# IO.net
KiCad netlist of a schematic drawn in Altium Designer
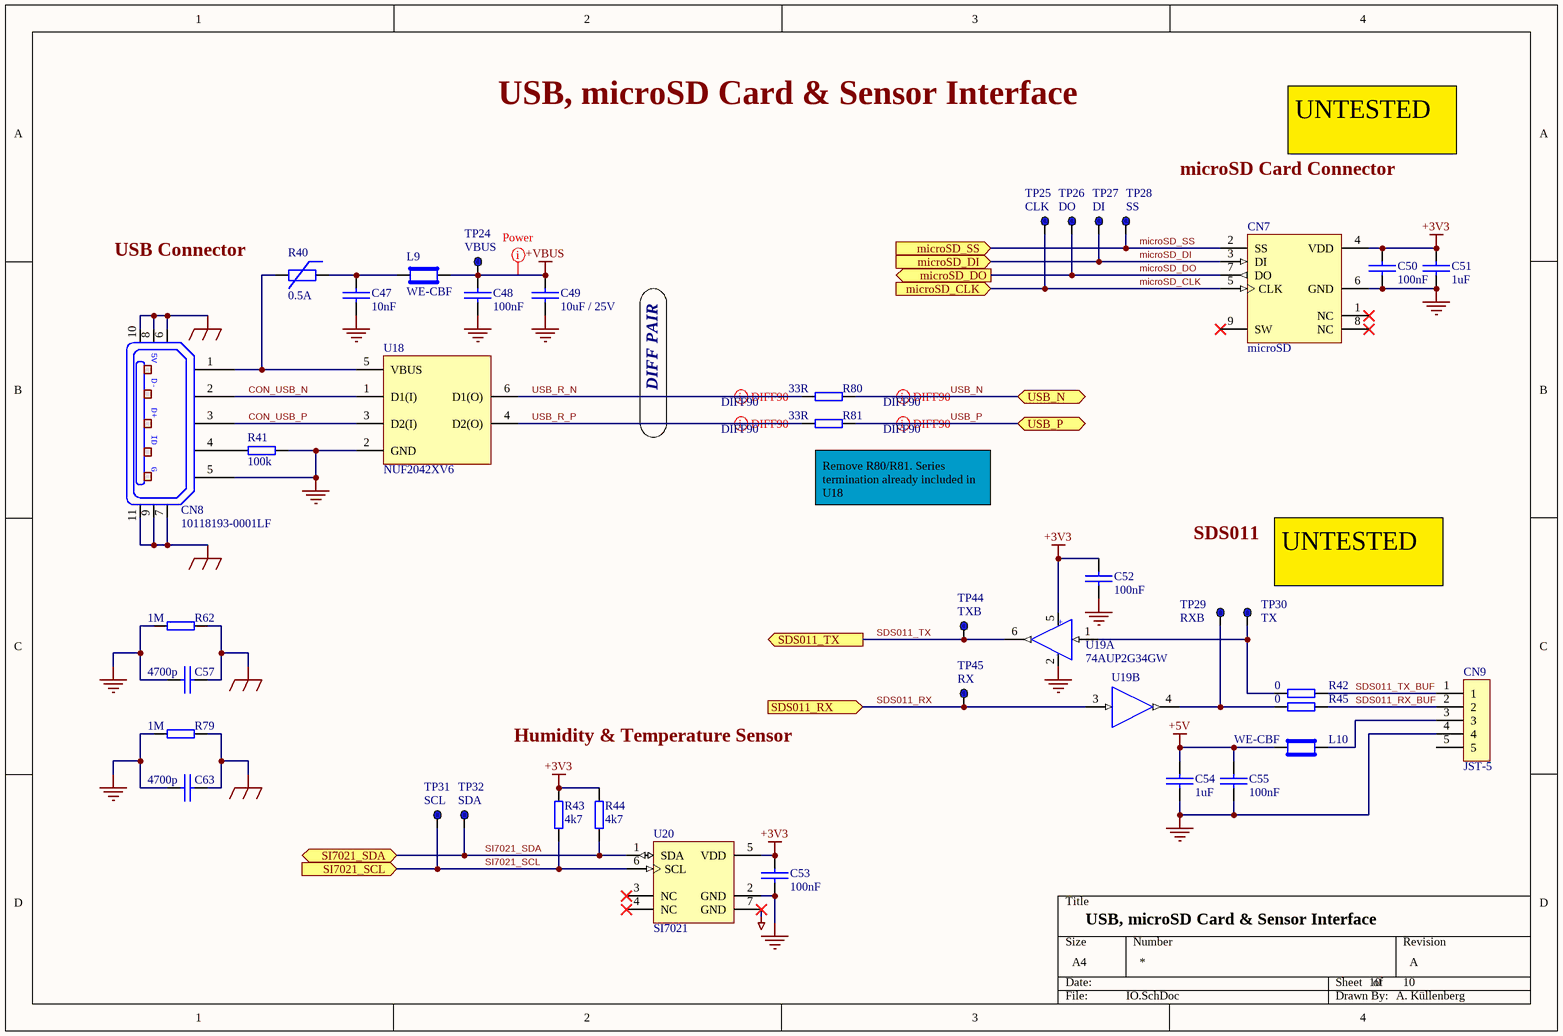
[diagram p0: IO.SchDoc]

(export (version "E")
  (design (tool "Eeschema 10.0.6"))
  (components
    (comp (ref "C47")
      (value "10nF")
      (footprint "C0603")
      (description "CAP CER 10000PF 50V X7R 0603")
      (fields (field (name "PART NUMBER") "06035C103KAT2A") (field (name "MANUFACTURER") "AVX Corporation"))
      (libsource (lib "AKLib") (part "CAP"))
    )
    (comp (ref "C48")
      (value "100nF")
      (footprint "C0603")
      (description "CAP CER 0.1UF 50V X7R 0603")
      (fields (field (name "PART NUMBER") "C0603C104K5RACTU") (field (name "MANUFACTURER") "Kemet"))
      (libsource (lib "AKLib") (part "CAP"))
    )
    (comp (ref "C49")
      (value "10uF / 25V")
      (footprint "C0603")
      (description "CAP CER 10UF 25V X5R 0603")
      (fields
        (field (name "PART NUMBER") "ZRB18AR61E106ME01L")
        (field (name "MANUFACTURER") "Murata Electronics North America")
      )
      (libsource (lib "AKLib") (part "CAP"))
    )
    (comp (ref "C50")
      (value "100nF")
      (footprint "C0603")
      (description "CAP CER 0.1UF 50V X7R 0603")
      (fields (field (name "PART NUMBER") "C0603C104K5RACTU") (field (name "MANUFACTURER") "Kemet"))
      (libsource (lib "AKLib") (part "CAP"))
    )
    (comp (ref "C51")
      (value "1uF")
      (footprint "C0603")
      (description "CAP CER 1UF 25V X7R 0603")
      (fields
        (field (name "PART NUMBER") "GCM188R71E105KA64D")
        (field (name "MANUFACTURER") "Murata Electronics North America")
      )
      (libsource (lib "AKLib") (part "CAP"))
    )
    (comp (ref "C52")
      (value "100nF")
      (footprint "C0603")
      (description "CAP CER 0.1UF 50V X7R 0603")
      (fields (field (name "PART NUMBER") "C0603C104K5RACTU") (field (name "MANUFACTURER") "Kemet"))
      (libsource (lib "AKLib") (part "CAP"))
    )
    (comp (ref "C53")
      (value "100nF")
      (footprint "C0603")
      (description "CAP CER 0.1UF 50V X7R 0603")
      (fields (field (name "PART NUMBER") "C0603C104K5RACTU") (field (name "MANUFACTURER") "Kemet"))
      (libsource (lib "AKLib") (part "CAP"))
    )
    (comp (ref "C54")
      (value "1uF")
      (footprint "C0603")
      (description "CAP CER 1UF 25V X7R 0603")
      (fields
        (field (name "PART NUMBER") "GCM188R71E105KA64D")
        (field (name "MANUFACTURER") "Murata Electronics North America")
      )
      (libsource (lib "AKLib") (part "CAP"))
    )
    (comp (ref "C55")
      (value "100nF")
      (footprint "C0603")
      (description "CAP CER 0.1UF 50V X7R 0603")
      (fields (field (name "PART NUMBER") "C0603C104K5RACTU") (field (name "MANUFACTURER") "Kemet"))
      (libsource (lib "AKLib") (part "CAP"))
    )
    (comp (ref "C57")
      (value "4700p")
      (footprint "C0805")
      (description "CAP CER 4700PF 1KV X7R 0805")
      (fields (field (name "PART NUMBER") "C0805V472KDRACTU") (field (name "MANUFACTURER") "KEMET"))
      (libsource (lib "AKLib") (part "CAP"))
    )
    (comp (ref "C63")
      (value "4700p")
      (footprint "C0805")
      (description "CAP CER 4700PF 1KV X7R 0805")
      (fields (field (name "PART NUMBER") "C0805V472KDRACTU") (field (name "MANUFACTURER") "KEMET"))
      (libsource (lib "AKLib") (part "CAP"))
    )
    (comp (ref "CN7")
      (value "microSD")
      (footprint "1050270001")
      (description "CONN MICRO SD CARD PUSH-PULL R/A")
      (fields (field (name "PART NUMBER") "1050270001") (field (name "MANUFACTURER") "Molex, LLC"))
      (libsource (lib "AKLib") (part "1050270001"))
    )
    (comp (ref "CN8")
      (value "10118193-0001LF")
      (footprint "10118193")
      (description "CONN USB MICRO B RECPT SMT R/A")
      (fields (field (name "MANUFACTURER") "Amphenol FCI"))
      (libsource (lib "AKLib") (part "10118193-0001LF"))
    )
    (comp (ref "CN9")
      (value "JST-5")
      (footprint "JST-5")
      (description "CONN HEADER XH TOP 5POS 2.5MM")
      (fields
        (field (name "PART NUMBER") "B5B-XH-A(LF)(SN)")
        (field (name "MANUFACTURER") "JST Sales America Inc.")
      )
      (libsource (lib "AKLib") (part "Header 1x5"))
    )
    (comp (ref "L9")
      (value "WE-CBF")
      (footprint "L0603")
      (description "FERRITE BEAD 600 OHM 0603 1LN")
      (fields (field (name "PART NUMBER") "742792651") (field (name "MANUFACTURER") "Wurth Electronics Inc."))
      (libsource (lib "AKLib") (part "FBEAD"))
    )
    (comp (ref "L10")
      (value "WE-CBF")
      (footprint "L0603")
      (description "FERRITE BEAD 600 OHM 0603 1LN")
      (fields (field (name "PART NUMBER") "742792651") (field (name "MANUFACTURER") "Wurth Electronics Inc."))
      (libsource (lib "AKLib") (part "FBEAD"))
    )
    (comp (ref "R40")
      (value "0.5A")
      (footprint "PTC-0603")
      (description "FUSE PTC RESET 500MA SMD 0603")
      (fields (field (name "PART NUMBER") "MF-FSMF050X-2") (field (name "MANUFACTURER") "Bourns Inc."))
      (libsource (lib "AKLib") (part "RES Varistor"))
    )
    (comp (ref "R41")
      (value "100k")
      (footprint "R0603")
      (description "RES SMD 100K OHM 1% 1/10W 0603")
      (fields (field (name "PART NUMBER") "RC0603FR-07100KL") (field (name "MANUFACTURER") "Yageo"))
      (libsource (lib "AKLib") (part "RES"))
    )
    (comp (ref "R42")
      (value "0")
      (footprint "R0603")
      (description "RES SMD 0.0OHM JUMPER 1/10W 0603")
      (fields (field (name "PART NUMBER") "RC0603JR-070RL") (field (name "MANUFACTURER") "Yageo"))
      (libsource (lib "AKLib") (part "RES"))
    )
    (comp (ref "R43")
      (value "4k7")
      (footprint "R0603")
      (description "RES SMD 4.7K OHM 1% 1/10W 0603")
      (fields (field (name "PART NUMBER") "CRCW06034K70FKEA") (field (name "MANUFACTURER") "Vishay Dale"))
      (libsource (lib "AKLib") (part "RES"))
    )
    (comp (ref "R44")
      (value "4k7")
      (footprint "R0603")
      (description "RES SMD 4.7K OHM 1% 1/10W 0603")
      (fields (field (name "PART NUMBER") "CRCW06034K70FKEA") (field (name "MANUFACTURER") "Vishay Dale"))
      (libsource (lib "AKLib") (part "RES"))
    )
    (comp (ref "R45")
      (value "0")
      (footprint "R0603")
      (description "RES SMD 0.0OHM JUMPER 1/10W 0603")
      (fields (field (name "PART NUMBER") "RC0603JR-070RL") (field (name "MANUFACTURER") "Yageo"))
      (libsource (lib "AKLib") (part "RES"))
    )
    (comp (ref "R62")
      (value "1M")
      (footprint "R0805")
      (description "RES SMD 1M OHM 1% 1/8W 0805")
      (fields (field (name "PART NUMBER") "RV0805FR-071ML") (field (name "MANUFACTURER") "Yageo"))
      (libsource (lib "AKLib") (part "RES"))
    )
    (comp (ref "R79")
      (value "1M")
      (footprint "R0805")
      (description "RES SMD 1M OHM 1% 1/8W 0805")
      (fields (field (name "PART NUMBER") "RV0805FR-071ML") (field (name "MANUFACTURER") "Yageo"))
      (libsource (lib "AKLib") (part "RES"))
    )
    (comp (ref "R80")
      (value "33R")
      (footprint "R0402")
      (description "RES SMD 33 OHM 1% 1/16W 0402")
      (fields (field (name "PART NUMBER") "RC0402FR-0733RL") (field (name "MANUFACTURER") "Yageo"))
      (libsource (lib "AKLib") (part "RES"))
    )
    (comp (ref "R81")
      (value "33R")
      (footprint "R0402")
      (description "RES SMD 33 OHM 1% 1/16W 0402")
      (fields (field (name "PART NUMBER") "RC0402FR-0733RL") (field (name "MANUFACTURER") "Yageo"))
      (libsource (lib "AKLib") (part "RES"))
    )
    (comp (ref "TP24")
      (value "VBUS")
      (footprint "TP_1mm")
      (fields (field (name "PART NUMBER") "TP"))
      (libsource (lib "AKLib") (part "TP"))
    )
    (comp (ref "TP25")
      (value "CLK")
      (footprint "TP_1mm")
      (fields (field (name "PART NUMBER") "TP"))
      (libsource (lib "AKLib") (part "TP"))
    )
    (comp (ref "TP26")
      (value "DO")
      (footprint "TP_1mm")
      (fields (field (name "PART NUMBER") "TP"))
      (libsource (lib "AKLib") (part "TP"))
    )
    (comp (ref "TP27")
      (value "DI")
      (footprint "TP_1mm")
      (fields (field (name "PART NUMBER") "TP"))
      (libsource (lib "AKLib") (part "TP"))
    )
    (comp (ref "TP28")
      (value "SS")
      (footprint "TP_1mm")
      (fields (field (name "PART NUMBER") "TP"))
      (libsource (lib "AKLib") (part "TP"))
    )
    (comp (ref "TP29")
      (value "RXB")
      (footprint "TP_1mm")
      (fields (field (name "PART NUMBER") "TP"))
      (libsource (lib "AKLib") (part "TP"))
    )
    (comp (ref "TP30")
      (value "TX")
      (footprint "TP_1mm")
      (fields (field (name "PART NUMBER") "TP"))
      (libsource (lib "AKLib") (part "TP"))
    )
    (comp (ref "TP31")
      (value "SCL")
      (footprint "TP_1mm")
      (fields (field (name "PART NUMBER") "TP"))
      (libsource (lib "AKLib") (part "TP"))
    )
    (comp (ref "TP32")
      (value "SDA")
      (footprint "TP_1mm")
      (fields (field (name "PART NUMBER") "TP"))
      (libsource (lib "AKLib") (part "TP"))
    )
    (comp (ref "TP44")
      (value "TXB")
      (footprint "TP_1mm")
      (fields (field (name "PART NUMBER") "TP"))
      (libsource (lib "AKLib") (part "TP"))
    )
    (comp (ref "TP45")
      (value "RX")
      (footprint "TP_1mm")
      (fields (field (name "PART NUMBER") "TP"))
      (libsource (lib "AKLib") (part "TP"))
    )
    (comp (ref "U18")
      (value "NUF2042XV6")
      (footprint "SOT-563")
      (description "FILTER RC(PI) 22 OHM/42PF SMD")
      (fields (field (name "PART NUMBER") "NUF2042XV6T1G") (field (name "MANUFACTURER") "ON Semiconductor"))
      (libsource (lib "AKLib") (part "NUF2042XV6"))
    )
    (comp (ref "U19")
      (value "74AUP2G34GW")
      (footprint "SOT363")
      (description "IC BUFF DL LOW PWR N-INV 6TSSOP")
      (fields
        (field (name "PART NUMBER") "74AUP2G34GW,125")
        (field (name "MANUFACTURER") "Nexperia USA Inc.")
      )
      (libsource (lib "AKLib") (part "74AUP2G34GW"))
    )
    (comp (ref "U20")
      (value "SI7021")
      (footprint "SI7021")
      (description "SENS HUMI/TEMP 3.6V I2C 3% 6DFN")
      (fields (field (name "PART NUMBER") "SI7021-A20-GM1") (field (name "MANUFACTURER") "Silicon Labs"))
      (libsource (lib "AKLib") (part "SI7021"))
    )
  )
  (nets
    (net (code "1") (name "+3V3") (class "Default")
      (node (ref "C50") (pin "2") (pinfunction "2_2") (pintype "passive"))
      (node (ref "C51") (pin "2") (pinfunction "2_2") (pintype "passive"))
      (node (ref "C52") (pin "2") (pinfunction "2_2") (pintype "passive"))
      (node (ref "C53") (pin "2") (pinfunction "2_2") (pintype "passive"))
      (node (ref "CN7") (pin "4") (pinfunction "VDD_4") (pintype "power_in"))
      (node (ref "R43") (pin "2") (pinfunction "2_2") (pintype "passive"))
      (node (ref "R44") (pin "2") (pinfunction "2_2") (pintype "passive"))
      (node (ref "U19") (pin "5") (pinfunction "5_5") (pintype "passive"))
      (node (ref "U20") (pin "5") (pinfunction "VDD_5") (pintype "power_in"))
    )
    (net (code "2") (name "+5V") (class "Default")
      (node (ref "C54") (pin "1") (pinfunction "1_1") (pintype "passive"))
      (node (ref "C55") (pin "1") (pinfunction "1_1") (pintype "passive"))
      (node (ref "L10") (pin "1") (pinfunction "1_1") (pintype "passive"))
    )
    (net (code "3") (name "+VBUS") (class "Default")
      (node (ref "C48") (pin "2") (pinfunction "2_2") (pintype "passive"))
      (node (ref "C49") (pin "2") (pinfunction "2_2") (pintype "passive"))
      (node (ref "L9") (pin "2") (pinfunction "2_2") (pintype "passive"))
      (node (ref "TP24") (pin "1") (pinfunction "1_1") (pintype "passive"))
    )
    (net (code "4") (name "/CON_USB_N") (class "Default")
      (node (ref "CN8") (pin "2") (pinfunction "2_2") (pintype "passive"))
      (node (ref "U18") (pin "1") (pinfunction "D1(I)_1") (pintype "passive"))
    )
    (net (code "5") (name "/CON_USB_P") (class "Default")
      (node (ref "CN8") (pin "3") (pinfunction "3_3") (pintype "passive"))
      (node (ref "U18") (pin "3") (pinfunction "D2(I)_3") (pintype "passive"))
    )
    (net (code "6") (name "/SDS011_RX") (class "Default")
      (node (ref "TP45") (pin "1") (pinfunction "1_1") (pintype "passive"))
      (node (ref "U19") (pin "3") (pinfunction "3_3") (pintype "input"))
    )
    (net (code "7") (name "/SDS011_RX_BUF") (class "Default")
      (node (ref "CN9") (pin "2") (pinfunction "2_2") (pintype "passive"))
      (node (ref "R45") (pin "2") (pinfunction "2_2") (pintype "passive"))
    )
    (net (code "8") (name "/SDS011_TX") (class "Default")
      (node (ref "TP44") (pin "1") (pinfunction "1_1") (pintype "passive"))
      (node (ref "U19") (pin "6") (pinfunction "6_6") (pintype "output"))
    )
    (net (code "9") (name "/SDS011_TX_BUF") (class "Default")
      (node (ref "CN9") (pin "1") (pinfunction "1_1") (pintype "passive"))
      (node (ref "R42") (pin "2") (pinfunction "2_2") (pintype "passive"))
    )
    (net (code "10") (name "/SI7021_SCL") (class "Default")
      (node (ref "R43") (pin "1") (pinfunction "1_1") (pintype "passive"))
      (node (ref "TP31") (pin "1") (pinfunction "1_1") (pintype "passive"))
      (node (ref "U20") (pin "6") (pinfunction "SCL_6") (pintype "input"))
    )
    (net (code "11") (name "/SI7021_SDA") (class "Default")
      (node (ref "R44") (pin "1") (pinfunction "1_1") (pintype "passive"))
      (node (ref "TP32") (pin "1") (pinfunction "1_1") (pintype "passive"))
      (node (ref "U20") (pin "1") (pinfunction "SDA_1") (pintype "bidirectional"))
    )
    (net (code "12") (name "/USB_N") (class "Default")
      (node (ref "R80") (pin "2") (pinfunction "2_2") (pintype "passive"))
    )
    (net (code "13") (name "/USB_P") (class "Default")
      (node (ref "R81") (pin "2") (pinfunction "2_2") (pintype "passive"))
    )
    (net (code "14") (name "/USB_R_N") (class "Default")
      (node (ref "R80") (pin "1") (pinfunction "1_1") (pintype "passive"))
      (node (ref "U18") (pin "6") (pinfunction "D1(O)_6") (pintype "passive"))
    )
    (net (code "15") (name "/USB_R_P") (class "Default")
      (node (ref "R81") (pin "1") (pinfunction "1_1") (pintype "passive"))
      (node (ref "U18") (pin "4") (pinfunction "D2(O)_4") (pintype "passive"))
    )
    (net (code "16") (name "/microSD_CLK") (class "Default")
      (node (ref "CN7") (pin "5") (pinfunction "CLK_5") (pintype "input"))
      (node (ref "TP25") (pin "1") (pinfunction "1_1") (pintype "passive"))
    )
    (net (code "17") (name "/microSD_DI") (class "Default")
      (node (ref "CN7") (pin "3") (pinfunction "DI_3") (pintype "input"))
      (node (ref "TP27") (pin "1") (pinfunction "1_1") (pintype "passive"))
    )
    (net (code "18") (name "/microSD_DO") (class "Default")
      (node (ref "CN7") (pin "7") (pinfunction "DO_7") (pintype "output"))
      (node (ref "TP26") (pin "1") (pinfunction "1_1") (pintype "passive"))
    )
    (net (code "19") (name "/microSD_SS") (class "Default")
      (node (ref "CN7") (pin "2") (pinfunction "SS_2") (pintype "passive"))
      (node (ref "TP28") (pin "1") (pinfunction "1_1") (pintype "passive"))
    )
    (net (code "20") (name "GND") (class "Default")
      (node (ref "C47") (pin "1") (pinfunction "1_1") (pintype "passive"))
      (node (ref "C48") (pin "1") (pinfunction "1_1") (pintype "passive"))
      (node (ref "C49") (pin "1") (pinfunction "1_1") (pintype "passive"))
      (node (ref "C50") (pin "1") (pinfunction "1_1") (pintype "passive"))
      (node (ref "C51") (pin "1") (pinfunction "1_1") (pintype "passive"))
      (node (ref "C52") (pin "1") (pinfunction "1_1") (pintype "passive"))
      (node (ref "C53") (pin "1") (pinfunction "1_1") (pintype "passive"))
      (node (ref "C54") (pin "2") (pinfunction "2_2") (pintype "passive"))
      (node (ref "C55") (pin "2") (pinfunction "2_2") (pintype "passive"))
      (node (ref "C57") (pin "1") (pinfunction "1_1") (pintype "passive"))
      (node (ref "C63") (pin "1") (pinfunction "1_1") (pintype "passive"))
      (node (ref "CN7") (pin "6") (pinfunction "GND_6") (pintype "power_in"))
      (node (ref "CN8") (pin "5") (pinfunction "5_5") (pintype "passive"))
      (node (ref "CN9") (pin "4") (pinfunction "4_4") (pintype "passive"))
      (node (ref "R41") (pin "2") (pinfunction "2_2") (pintype "passive"))
      (node (ref "R62") (pin "1") (pinfunction "1_1") (pintype "passive"))
      (node (ref "R79") (pin "1") (pinfunction "1_1") (pintype "passive"))
      (node (ref "U18") (pin "2") (pinfunction "GND_2") (pintype "power_in"))
      (node (ref "U19") (pin "2") (pinfunction "2_2") (pintype "power_in"))
      (node (ref "U20") (pin "2") (pinfunction "GND_2") (pintype "power_in"))
    )
    (net (code "21") (name "Net-(C47-Pad2)") (class "Default")
      (node (ref "C47") (pin "2") (pinfunction "2_2") (pintype "passive"))
      (node (ref "L9") (pin "1") (pinfunction "1_1") (pintype "passive"))
      (node (ref "R40") (pin "1") (pinfunction "1_1") (pintype "passive"))
    )
    (net (code "22") (name "Net-(CN8-Pad4)") (class "Default")
      (node (ref "CN8") (pin "4") (pinfunction "4_4") (pintype "passive"))
      (node (ref "R41") (pin "1") (pinfunction "1_1") (pintype "passive"))
    )
    (net (code "23") (name "Net-(CN9-Pad3)") (class "Default")
      (node (ref "CN9") (pin "3") (pinfunction "3_3") (pintype "passive"))
      (node (ref "L10") (pin "2") (pinfunction "2_2") (pintype "passive"))
    )
    (net (code "24") (name "Net-(R42-Pad1)") (class "Default")
      (node (ref "R42") (pin "1") (pinfunction "1_1") (pintype "passive"))
      (node (ref "TP30") (pin "1") (pinfunction "1_1") (pintype "passive"))
      (node (ref "U19") (pin "1") (pinfunction "1_1") (pintype "input"))
    )
    (net (code "25") (name "Net-(R45-Pad1)") (class "Default")
      (node (ref "R45") (pin "1") (pinfunction "1_1") (pintype "passive"))
      (node (ref "TP29") (pin "1") (pinfunction "1_1") (pintype "passive"))
      (node (ref "U19") (pin "4") (pinfunction "4_4") (pintype "output"))
    )
    (net (code "26") (name "Net-(U18-VBUS)") (class "Default")
      (node (ref "CN8") (pin "1") (pinfunction "1_1") (pintype "passive"))
      (node (ref "R40") (pin "2") (pinfunction "2_2") (pintype "passive"))
      (node (ref "U18") (pin "5") (pinfunction "VBUS_5") (pintype "power_in"))
    )
    (net (code "27") (name "SHIELD") (class "Default")
      (node (ref "C57") (pin "2") (pinfunction "2_2") (pintype "passive"))
      (node (ref "C63") (pin "2") (pinfunction "2_2") (pintype "passive"))
      (node (ref "CN8") (pin "10") (pinfunction "10_10") (pintype "passive"))
      (node (ref "CN8") (pin "11") (pinfunction "11_11") (pintype "passive"))
      (node (ref "CN8") (pin "6") (pinfunction "6_6") (pintype "passive"))
      (node (ref "CN8") (pin "7") (pinfunction "7_7") (pintype "passive"))
      (node (ref "CN8") (pin "8") (pinfunction "8_8") (pintype "passive"))
      (node (ref "CN8") (pin "9") (pinfunction "9_9") (pintype "passive"))
      (node (ref "R62") (pin "2") (pinfunction "2_2") (pintype "passive"))
      (node (ref "R79") (pin "2") (pinfunction "2_2") (pintype "passive"))
    )
    (net (code "28") (name "TH1") (class "Default")
      (node (ref "U20") (pin "7") (pinfunction "GND_7") (pintype "power_in"))
    )
    (net (code "29") (name "unconnected-(CN7-NC-Pad1)") (class "Default")
      (node (ref "CN7") (pin "1") (pinfunction "NC_1") (pintype "passive+no_connect"))
    )
    (net (code "30") (name "unconnected-(CN7-NC-Pad8)") (class "Default")
      (node (ref "CN7") (pin "8") (pinfunction "NC_8") (pintype "passive+no_connect"))
    )
    (net (code "31") (name "unconnected-(CN7-SW-Pad9)") (class "Default")
      (node (ref "CN7") (pin "9") (pinfunction "SW_9") (pintype "passive+no_connect"))
    )
    (net (code "32") (name "unconnected-(CN9-Pad5)") (class "Default")
      (node (ref "CN9") (pin "5") (pinfunction "5_5") (pintype "passive"))
    )
    (net (code "33") (name "unconnected-(U20-NC-Pad3)") (class "Default")
      (node (ref "U20") (pin "3") (pinfunction "NC_3") (pintype "passive+no_connect"))
    )
    (net (code "34") (name "unconnected-(U20-NC-Pad4)") (class "Default")
      (node (ref "U20") (pin "4") (pinfunction "NC_4") (pintype "passive+no_connect"))
    )
  )
)
